# T962a-P1.net
KiCad netlist of a schematic drawn in Altium Designer
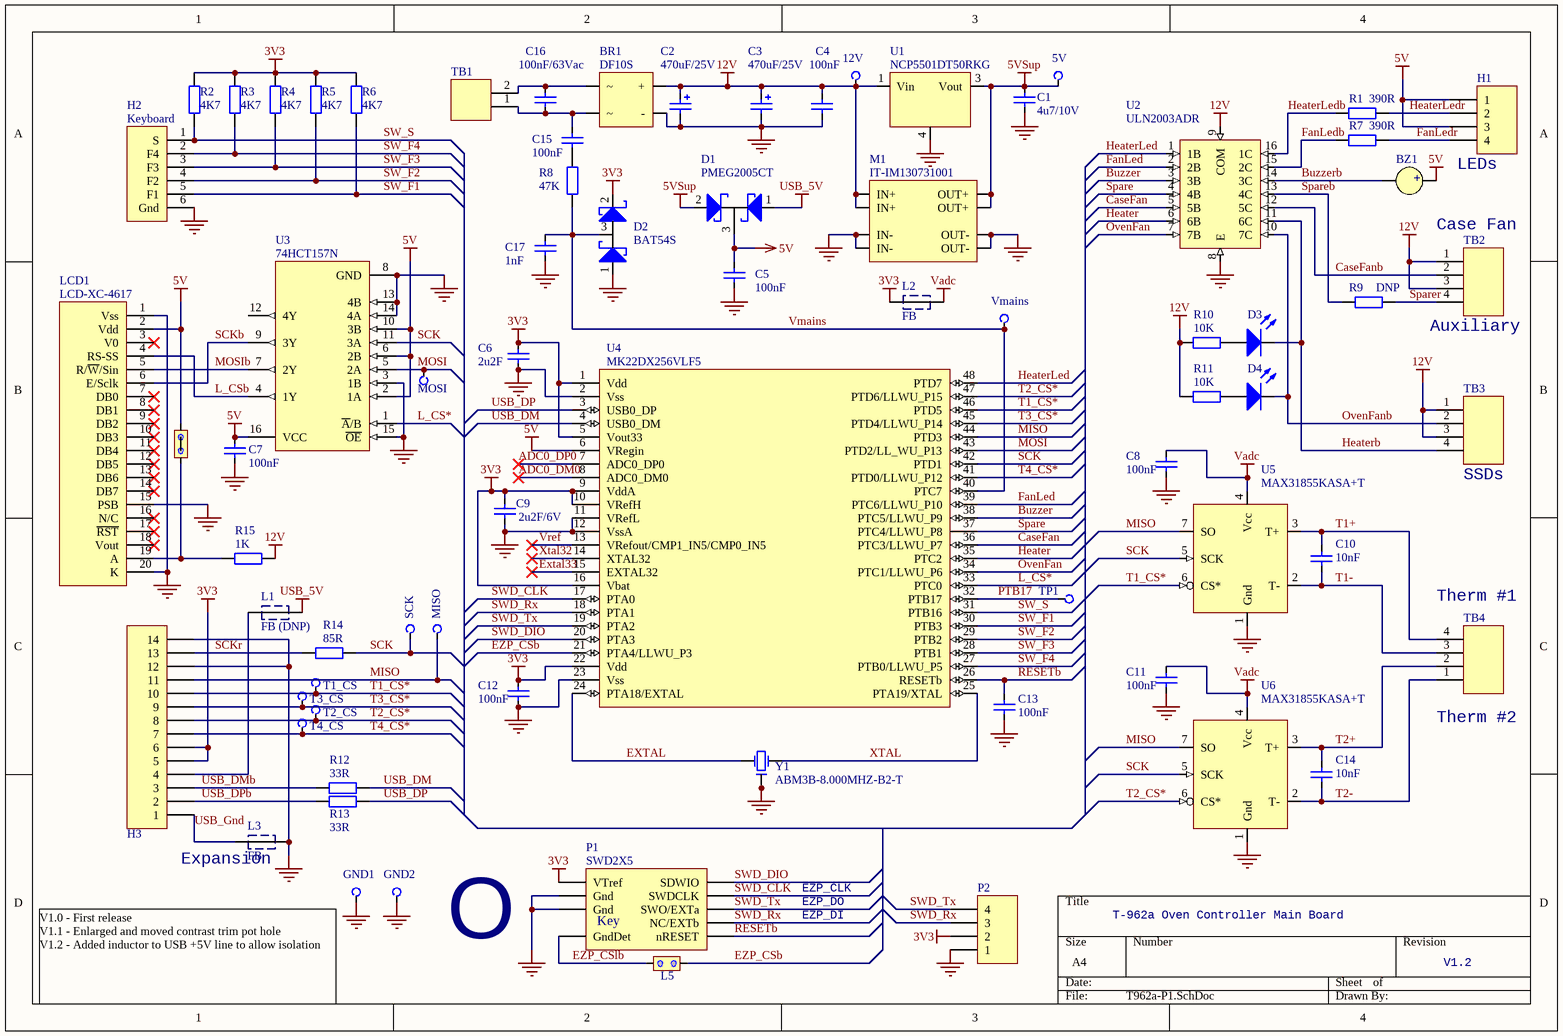
[diagram p0: T962a-P1.SchDoc]

(export (version "E")
  (design (tool "Eeschema 10.0.6"))
  (components
    (comp (ref "5V")
      (value "TP")
      (footprint "PCBPIN - 0.9mm")
      (description "Test Point")
      (libsource (lib "MyLibrary") (part "TP"))
    )
    (comp (ref "12V")
      (value "TP")
      (footprint "PCBPIN - 0.9mm")
      (description "Test Point")
      (libsource (lib "MyLibrary") (part "TP"))
    )
    (comp (ref "BR1")
      (value "DF10S")
      (footprint "Bridge-SMT")
      (description "bRIDGE rECTIFIER")
      (libsource (lib "MySchLib") (part "DF10S"))
    )
    (comp (ref "BZ1")
      (value "Buzzer_PCB")
      (footprint "BUZZER_Small")
      (description "Buzzer (Adafruit 1536)")
      (libsource (lib "MyLibrary") (part "Buzzer_PCB"))
    )
    (comp (ref "C1")
      (value "4u7/10V")
      (footprint "CCNP2012-0805")
      (description "Capacitor SMT 0805")
      (fields
        (field (name "MANUFACTURER") "Generic Components")
        (field (name "PUBLISHER") "Altium Hobart Technology Centre")
      )
      (libsource (lib "MyLibrary") (part "Cap_CCNP_0805"))
    )
    (comp (ref "C2")
      (value "470uF/25V")
      (footprint "RB5/10x13mm")
      (description "Polarized Capacitor")
      (fields
        (field (name "MANUFACTURER") "Generic Components")
        (field (name "PUBLISHER") "Altium Hobart Technology Centre")
      )
      (libsource (lib "MySchLib") (part "Cap-25ZLS470MEFC10X12"))
    )
    (comp (ref "C3")
      (value "470uF/25V")
      (footprint "RB5/10x13mm")
      (description "Polarized Capacitor")
      (fields
        (field (name "MANUFACTURER") "Generic Components")
        (field (name "PUBLISHER") "Altium Hobart Technology Centre")
      )
      (libsource (lib "MySchLib") (part "Cap-25ZLS470MEFC10X12"))
    )
    (comp (ref "C4")
      (value "100nF")
      (footprint "CCNP2012-0805")
      (description "Capacitor")
      (fields
        (field (name "MANUFACTURER") "Generic Components")
        (field (name "PUBLISHER") "Altium Hobart Technology Centre")
      )
      (libsource (lib "MyLibrary") (part "Cap"))
    )
    (comp (ref "C5")
      (value "100nF")
      (footprint "CCNP2012-0805")
      (description "Capacitor")
      (fields
        (field (name "MANUFACTURER") "Generic Components")
        (field (name "PUBLISHER") "Altium Hobart Technology Centre")
      )
      (libsource (lib "MyLibrary") (part "Cap"))
    )
    (comp (ref "C6")
      (value "2u2F")
      (footprint "CCNP2012-0805")
      (description "Capacitor")
      (fields
        (field (name "MANUFACTURER") "Generic Components")
        (field (name "PUBLISHER") "Altium Hobart Technology Centre")
      )
      (libsource (lib "MyLibrary") (part "Cap"))
    )
    (comp (ref "C7")
      (value "100nF")
      (footprint "CCNP2012-0805")
      (description "Capacitor")
      (fields
        (field (name "MANUFACTURER") "Generic Components")
        (field (name "PUBLISHER") "Altium Hobart Technology Centre")
      )
      (libsource (lib "MyLibrary") (part "Cap"))
    )
    (comp (ref "C8")
      (value "100nF")
      (footprint "CCNP2012-0805")
      (description "Capacitor SMT 0805")
      (fields
        (field (name "MANUFACTURER") "Generic Components")
        (field (name "PUBLISHER") "Altium Hobart Technology Centre")
      )
      (libsource (lib "MyLibrary") (part "Cap_CCNP_0805"))
    )
    (comp (ref "C9")
      (value "2u2F/6V")
      (footprint "CCNP2012-0805")
      (description "Capacitor")
      (fields
        (field (name "MANUFACTURER") "Generic Components")
        (field (name "PUBLISHER") "Altium Hobart Technology Centre")
      )
      (libsource (lib "MyLibrary") (part "Cap"))
    )
    (comp (ref "C10")
      (value "10nF")
      (footprint "CCNP2012-0805")
      (description "Capacitor SMT 0805")
      (fields
        (field (name "MANUFACTURER") "Generic Components")
        (field (name "PUBLISHER") "Altium Hobart Technology Centre")
      )
      (libsource (lib "MyLibrary") (part "Cap_CCNP_0805"))
    )
    (comp (ref "C11")
      (value "100nF")
      (footprint "CCNP2012-0805")
      (description "Capacitor SMT 0805")
      (fields
        (field (name "MANUFACTURER") "Generic Components")
        (field (name "PUBLISHER") "Altium Hobart Technology Centre")
      )
      (libsource (lib "MyLibrary") (part "Cap_CCNP_0805"))
    )
    (comp (ref "C12")
      (value "100nF")
      (footprint "CCNP2012-0805")
      (description "Capacitor")
      (fields
        (field (name "MANUFACTURER") "Generic Components")
        (field (name "PUBLISHER") "Altium Hobart Technology Centre")
      )
      (libsource (lib "MyLibrary") (part "Cap"))
    )
    (comp (ref "C13")
      (value "100nF")
      (footprint "CCNP2012-0805")
      (description "Capacitor SMT 0805")
      (fields
        (field (name "MANUFACTURER") "Generic Components")
        (field (name "PUBLISHER") "Altium Hobart Technology Centre")
      )
      (libsource (lib "MyLibrary") (part "Cap_CCNP_0805"))
    )
    (comp (ref "C14")
      (value "10nF")
      (footprint "CCNP2012-0805")
      (description "Capacitor SMT 0805")
      (fields
        (field (name "MANUFACTURER") "Generic Components")
        (field (name "PUBLISHER") "Altium Hobart Technology Centre")
      )
      (libsource (lib "MyLibrary") (part "Cap_CCNP_0805"))
    )
    (comp (ref "C15")
      (value "100nF")
      (footprint "CCNP2012-0805")
      (description "Capacitor")
      (fields
        (field (name "MANUFACTURER") "Generic Components")
        (field (name "PUBLISHER") "Altium Hobart Technology Centre")
      )
      (libsource (lib "MyLibrary") (part "Cap"))
    )
    (comp (ref "C16")
      (value "100nF/63Vac")
      (footprint "CAP - small MKT")
      (description "Capacitor")
      (fields
        (field (name "MANUFACTURER") "Generic Components")
        (field (name "PUBLISHER") "Altium Hobart Technology Centre")
      )
      (libsource (lib "MyLibrary") (part "Cap"))
    )
    (comp (ref "C17")
      (value "1nF")
      (footprint "CCNP2012-0805")
      (description "Capacitor")
      (fields
        (field (name "MANUFACTURER") "Generic Components")
        (field (name "PUBLISHER") "Altium Hobart Technology Centre")
      )
      (libsource (lib "MyLibrary") (part "Cap"))
    )
    (comp (ref "D1")
      (value "PMEG2005CT")
      (footprint "SOT23")
      (description "Dual Schottky Diode (SMT)")
      (libsource (lib "MyLibrary") (part "PMEG2005CT"))
    )
    (comp (ref "D2")
      (value "BAT54S")
      (footprint "SOT23")
      (description "Dual Diode (SMT)")
      (libsource (lib "MyLibrary") (part "BAT54S"))
    )
    (comp (ref "D3")
      (value "LED Red")
      (footprint "LED-SMT-2")
      (description "LED (Red SMT)")
      (fields (field (name "MANUFACTURER") "Generic Components") (field (name "PUBLISHER") "Altium Limited"))
      (libsource (lib "MyLibrary") (part "LED SMT,Red"))
    )
    (comp (ref "D4")
      (value "LED Red")
      (footprint "LED-SMT-2")
      (description "LED (Red SMT)")
      (fields (field (name "MANUFACTURER") "Generic Components") (field (name "PUBLISHER") "Altium Limited"))
      (libsource (lib "MyLibrary") (part "LED SMT,Red"))
    )
    (comp (ref "GND1")
      (value "TP")
      (footprint "PCBPIN - 0.9mm")
      (description "Test Point")
      (libsource (lib "MyLibrary") (part "TP"))
    )
    (comp (ref "GND2")
      (value "TP")
      (footprint "PCBPIN - 0.9mm")
      (description "Test Point")
      (libsource (lib "MyLibrary") (part "TP"))
    )
    (comp (ref "H1")
      (value "Header 1x4")
      (footprint "HDR1X4S")
      (description "Header, 5-Pin, Right Angle")
      (fields (field (name "PUBLISHER") "Altium Limited"))
      (libsource (lib "") (part "Header 1x4_1"))
    )
    (comp (ref "H2")
      (value "Keyboard")
      (footprint "HDR1X6H")
      (description "Header, 6-Pin")
      (fields (field (name "PUBLISHER") "Altium Limited"))
      (libsource (lib "Miscellaneous Connectors") (part "Header 6"))
    )
    (comp (ref "H3")
      (value "2x5 Header")
      (footprint "HDR2X7H")
      (description "Header 2x7")
      (libsource (lib "MyLibrary") (part "Header 2x7H"))
    )
    (comp (ref "L1")
      (value "FB (DNP)")
      (footprint "CR2012-0805")
      (description "Ferrite Bead (0805) 0.045OHM, 2A")
      (libsource (lib "MyLibrary") (part "Ferrite Bead 0805"))
    )
    (comp (ref "L2")
      (value "FB")
      (footprint "CR2012-0805")
      (description "Ferrite Bead (0805) 0.045OHM, 2A")
      (libsource (lib "MyLibrary") (part "Ferrite Bead 0805"))
    )
    (comp (ref "L3")
      (value "FB")
      (footprint "CR2012-0805")
      (description "Ferrite Bead (0805) 0.045OHM, 2A")
      (libsource (lib "MyLibrary") (part "Ferrite Bead 0805"))
    )
    (comp (ref "L5")
      (value "LinkOpen")
      (footprint "SolderBridge(Open)")
      (libsource (lib "MyLibrary") (part "LinkOpen"))
    )
    (comp (ref "L6")
      (value "LinkClosed")
      (footprint "SolderBridge(Closed)")
      (libsource (lib "MyLibrary") (part "LinkClosed"))
    )
    (comp (ref "LCD1")
      (value "LCD-XC-4617")
      (footprint "LCD_XC-4617")
      (description "LCD 128 x 64 pixel, ST7920 controller & contrast pot (Jaycar XC-4617)")
      (libsource (lib "MyLibrary") (part "LCD-XC-4617"))
    )
    (comp (ref "Logo1")
      (value "OSHW Logo")
      (footprint "OSHW")
      (libsource (lib "MyLibrary") (part "OSHW Logo"))
    )
    (comp (ref "M1")
      (value "IT-IM130731001")
      (footprint "IT-IM130731001")
      (description "Itead Buck converter")
      (libsource (lib "MyLibrary") (part "IT-IM130731001"))
    )
    (comp (ref "MISO")
      (value "TP")
      (footprint "PCBPIN - 0.9mm")
      (description "Test Point")
      (libsource (lib "MyLibrary") (part "TP"))
    )
    (comp (ref "MOSI")
      (value "TP")
      (footprint "PCBPIN - 0.9mm")
      (description "Test Point")
      (libsource (lib "MyLibrary") (part "TP"))
    )
    (comp (ref "P1")
      (value "SWD2X5")
      (footprint "SWD-2x5")
      (description "SWD Connector 2x5-Pin")
      (fields (field (name "PUBLISHER") "Altium Limited"))
      (libsource (lib "MySchLib") (part "SWD2X5"))
    )
    (comp (ref "P2")
      (value "Header 1x4")
      (footprint "HDR1X4S")
      (description "Header, 5-Pin, Right Angle")
      (fields (field (name "PUBLISHER") "Altium Limited"))
      (libsource (lib "MyLibrary") (part "Header 1x4"))
    )
    (comp (ref "R1")
      (value "390R")
      (footprint "CR2012-0805")
      (description "Resistor")
      (fields
        (field (name "MANUFACTURER") "Generic Components")
        (field (name "PUBLISHER") "Altium Hobart Technology Centre")
      )
      (libsource (lib "") (part "Res_CR0805_1"))
    )
    (comp (ref "R2")
      (value "4K7")
      (footprint "CR2012-0805")
      (description "Resistor")
      (fields
        (field (name "MANUFACTURER") "Generic Components")
        (field (name "PUBLISHER") "Altium Hobart Technology Centre")
      )
      (libsource (lib "MyLibrary") (part "Res_CR0805"))
    )
    (comp (ref "R3")
      (value "4K7")
      (footprint "CR2012-0805")
      (description "Resistor")
      (fields
        (field (name "MANUFACTURER") "Generic Components")
        (field (name "PUBLISHER") "Altium Hobart Technology Centre")
      )
      (libsource (lib "MyLibrary") (part "Res_CR0805"))
    )
    (comp (ref "R4")
      (value "4K7")
      (footprint "CR2012-0805")
      (description "Resistor")
      (fields
        (field (name "MANUFACTURER") "Generic Components")
        (field (name "PUBLISHER") "Altium Hobart Technology Centre")
      )
      (libsource (lib "MyLibrary") (part "Res_CR0805"))
    )
    (comp (ref "R5")
      (value "4K7")
      (footprint "CR2012-0805")
      (description "Resistor")
      (fields
        (field (name "MANUFACTURER") "Generic Components")
        (field (name "PUBLISHER") "Altium Hobart Technology Centre")
      )
      (libsource (lib "MyLibrary") (part "Res_CR0805"))
    )
    (comp (ref "R6")
      (value "4K7")
      (footprint "CR2012-0805")
      (description "Resistor")
      (fields
        (field (name "MANUFACTURER") "Generic Components")
        (field (name "PUBLISHER") "Altium Hobart Technology Centre")
      )
      (libsource (lib "MyLibrary") (part "Res_CR0805"))
    )
    (comp (ref "R7")
      (value "390R")
      (footprint "CR2012-0805")
      (description "Resistor")
      (fields
        (field (name "MANUFACTURER") "Generic Components")
        (field (name "PUBLISHER") "Altium Hobart Technology Centre")
      )
      (libsource (lib "") (part "Res_CR0805_1"))
    )
    (comp (ref "R8")
      (value "47K")
      (footprint "CR2012-0805")
      (description "Resistor")
      (fields
        (field (name "MANUFACTURER") "Generic Components")
        (field (name "PUBLISHER") "Altium Hobart Technology Centre")
      )
      (libsource (lib "MyLibrary") (part "Res_CR0805"))
    )
    (comp (ref "R9")
      (value "DNP")
      (footprint "CR2012-0805")
      (description "Resistor")
      (fields
        (field (name "MANUFACTURER") "Generic Components")
        (field (name "PUBLISHER") "Altium Hobart Technology Centre")
      )
      (libsource (lib "") (part "Res_CR0805_1"))
    )
    (comp (ref "R10")
      (value "10K")
      (footprint "CR2012-0805")
      (description "Resistor")
      (fields
        (field (name "MANUFACTURER") "Generic Components")
        (field (name "PUBLISHER") "Altium Hobart Technology Centre")
      )
      (libsource (lib "") (part "Res_CR0805_1"))
    )
    (comp (ref "R11")
      (value "10K")
      (footprint "CR2012-0805")
      (description "Resistor")
      (fields
        (field (name "MANUFACTURER") "Generic Components")
        (field (name "PUBLISHER") "Altium Hobart Technology Centre")
      )
      (libsource (lib "") (part "Res_CR0805_1"))
    )
    (comp (ref "R12")
      (value "33R")
      (footprint "CR2012-0805")
      (description "Resistor")
      (fields
        (field (name "MANUFACTURER") "Generic Components")
        (field (name "PUBLISHER") "Altium Hobart Technology Centre")
      )
      (libsource (lib "MyLibrary") (part "Res_CR0805"))
    )
    (comp (ref "R13")
      (value "33R")
      (footprint "CR2012-0805")
      (description "Resistor")
      (fields
        (field (name "MANUFACTURER") "Generic Components")
        (field (name "PUBLISHER") "Altium Hobart Technology Centre")
      )
      (libsource (lib "MyLibrary") (part "Res_CR0805"))
    )
    (comp (ref "R14")
      (value "85R")
      (footprint "CR2012-0805")
      (description "Resistor")
      (fields
        (field (name "MANUFACTURER") "Generic Components")
        (field (name "PUBLISHER") "Altium Hobart Technology Centre")
      )
      (libsource (lib "MyLibrary") (part "Res_CR0805"))
    )
    (comp (ref "R15")
      (value "1K")
      (footprint "CR2012-0805")
      (description "Resistor")
      (fields
        (field (name "MANUFACTURER") "Generic Components")
        (field (name "PUBLISHER") "Altium Hobart Technology Centre")
      )
      (libsource (lib "MyLibrary") (part "Res_CR0805"))
    )
    (comp (ref "SCK")
      (value "TP")
      (footprint "PCBPIN - 0.9mm")
      (description "Test Point")
      (libsource (lib "MyLibrary") (part "TP"))
    )
    (comp (ref "T1_CS")
      (value "TP")
      (footprint "PCBPIN - 0.9mm")
      (description "Test Point")
      (libsource (lib "MyLibrary") (part "TP"))
    )
    (comp (ref "T2_CS")
      (value "TP")
      (footprint "PCBPIN - 0.9mm")
      (description "Test Point")
      (libsource (lib "MyLibrary") (part "TP"))
    )
    (comp (ref "T3_CS")
      (value "TP")
      (footprint "PCBPIN - 0.9mm")
      (description "Test Point")
      (libsource (lib "MyLibrary") (part "TP"))
    )
    (comp (ref "T4_CS")
      (value "TP")
      (footprint "PCBPIN - 0.9mm")
      (description "Test Point")
      (libsource (lib "MyLibrary") (part "TP"))
    )
    (comp (ref "TB1")
      (value "Terminal2")
      (footprint "MOLEX-39544-3002")
      (description "MULTICOMP  MC24366 Wire-To-Board Terminal Block")
      (libsource (lib "MyLibrary") (part "Terminal2"))
    )
    (comp (ref "TB2")
      (value "Terminal4")
      (footprint "MOLEX-39544-3004")
      (description "MULTICOMP MC24368 Wire-To-Board Terminal Block")
      (libsource (lib "MyLibrary") (part "Terminal4"))
    )
    (comp (ref "TB3")
      (value "Terminal4")
      (footprint "MOLEX-39544-3004")
      (description "MULTICOMP MC24368 Wire-To-Board Terminal Block")
      (libsource (lib "MyLibrary") (part "Terminal4"))
    )
    (comp (ref "TB4")
      (value "Terminal4")
      (footprint "MOLEX-39544-3004")
      (description "MULTICOMP MC24368 Wire-To-Board Terminal Block")
      (libsource (lib "") (part "Terminal4_1"))
    )
    (comp (ref "TP1")
      (value "TP")
      (footprint "PCBPIN - 0.9mm")
      (description "Test Point")
      (libsource (lib "MyLibrary") (part "TP"))
    )
    (comp (ref "U1")
      (value "NCP5501DT50RKG")
      (footprint "TO-252")
      (description "Fixed LDO Voltage Regulator, 2.5V-16V in, 230mV Dropout, 5V/500mA out, TO-252-3")
      (libsource (lib "MyLibrary") (part "NCP5501DT50RKG"))
    )
    (comp (ref "U2")
      (value "ULN2003ADR")
      (footprint "SO-16_N")
      (libsource (lib "MyLibrary") (part "ULN2003ADR"))
    )
    (comp (ref "U3")
      (value "74HCT157N")
      (footprint "SO-16_N")
      (description "Quad 2-1 Multiplexor")
      (libsource (lib "MyLibrary") (part "74HCT157N"))
    )
    (comp (ref "U4")
      (value "MK22DX256VLF5")
      (footprint "TSQFP50P900X900-48M")
      (description "Arm Cortex M4")
      (libsource (lib "MyLibrary") (part "MK22DX256VLF5"))
    )
    (comp (ref "U5")
      (value "MAX31855KASA+T")
      (footprint "SO-8_L")
      (libsource (lib "MySchLib") (part "MAX31855KASA+T"))
    )
    (comp (ref "U6")
      (value "MAX31855KASA+T")
      (footprint "SO-8_L")
      (libsource (lib "MySchLib") (part "MAX31855KASA+T"))
    )
    (comp (ref "Vmains")
      (value "TP")
      (footprint "PCBPIN - 0.9mm")
      (description "Test Point")
      (libsource (lib "MyLibrary") (part "TP"))
    )
    (comp (ref "Y1")
      (value "ABM3B-8.000MHZ-B2-T")
      (footprint "Crystal_SMT - ABM3B")
      (description "Crystal 8MHz (MINIATURE SMT ABM3B)")
      (fields
        (field (name "MANUFACTURER") "Generic Components")
        (field (name "PUBLISHER") "Altium Hobart Technology Centre")
      )
      (libsource (lib "MyLibrary") (part "ABM3B-8.000MHZ-B2-T"))
    )
  )
  (nets
    (net (code "1") (name "/ADC0_DM0") (class "Default")
      (node (ref "U4") (pin "8") (pinfunction "ADC0_DM0_8") (pintype "passive+no_connect"))
    )
    (net (code "2") (name "/ADC0_DP0") (class "Default")
      (node (ref "U4") (pin "7") (pinfunction "ADC0_DP0_7") (pintype "passive+no_connect"))
    )
    (net (code "3") (name "/Buzzer") (class "Default")
      (node (ref "U2") (pin "3") (pinfunction "3B_3") (pintype "input"))
      (node (ref "U4") (pin "38") (pinfunction "PTC5/LLWU_P9_38") (pintype "bidirectional"))
    )
    (net (code "4") (name "/Buzzerb") (class "Default")
      (node (ref "BZ1") (pin "1") (pinfunction "1_1") (pintype "passive"))
      (node (ref "U2") (pin "14") (pinfunction "3C_14") (pintype "input"))
    )
    (net (code "5") (name "/CaseFan") (class "Default")
      (node (ref "U2") (pin "5") (pinfunction "5B_5") (pintype "input"))
      (node (ref "U4") (pin "36") (pinfunction "PTC3/LLWU_P7_36") (pintype "bidirectional"))
    )
    (net (code "6") (name "/CaseFanb") (class "Default")
      (node (ref "TB2") (pin "2") (pinfunction "2_2") (pintype "passive"))
      (node (ref "U2") (pin "12") (pinfunction "5C_12") (pintype "input"))
    )
    (net (code "7") (name "/EXTAL") (class "Default")
      (node (ref "U4") (pin "24") (pinfunction "PTA18/EXTAL_24") (pintype "bidirectional"))
      (node (ref "Y1") (pin "1") (pinfunction "OSC1_1") (pintype "passive"))
    )
    (net (code "8") (name "/EZP_CSb") (class "Default")
      (node (ref "L5") (pin "2") (pintype "passive"))
      (node (ref "U4") (pin "21") (pinfunction "PTA4/LLWU_P3_21") (pintype "bidirectional"))
    )
    (net (code "9") (name "/EZP_CSlb") (class "Default")
      (node (ref "L5") (pin "1") (pintype "passive"))
      (node (ref "P1") (pin "9") (pinfunction "GndDet_9") (pintype "passive"))
    )
    (net (code "10") (name "/Extal33") (class "Default")
      (node (ref "U4") (pin "15") (pinfunction "EXTAL32_15") (pintype "passive+no_connect"))
    )
    (net (code "11") (name "/FanLed") (class "Default")
      (node (ref "U2") (pin "2") (pinfunction "2B_2") (pintype "input"))
      (node (ref "U4") (pin "39") (pinfunction "PTC6/LLWU_P10_39") (pintype "bidirectional"))
    )
    (net (code "12") (name "/FanLedb") (class "Default")
      (node (ref "R7") (pin "1") (pinfunction "1_1") (pintype "passive"))
      (node (ref "U2") (pin "15") (pinfunction "2C_15") (pintype "input"))
    )
    (net (code "13") (name "/FanLedr") (class "Default")
      (node (ref "H1") (pin "4") (pinfunction "4_4") (pintype "passive"))
      (node (ref "R7") (pin "2") (pinfunction "2_2") (pintype "passive"))
    )
    (net (code "14") (name "/Heater") (class "Default")
      (node (ref "U2") (pin "6") (pinfunction "6B_6") (pintype "input"))
      (node (ref "U4") (pin "35") (pinfunction "PTC2_35") (pintype "bidirectional"))
    )
    (net (code "15") (name "/HeaterLed") (class "Default")
      (node (ref "U2") (pin "1") (pinfunction "1B_1") (pintype "input"))
      (node (ref "U4") (pin "48") (pinfunction "PTD7_48") (pintype "bidirectional"))
    )
    (net (code "16") (name "/HeaterLedb") (class "Default")
      (node (ref "R1") (pin "1") (pinfunction "1_1") (pintype "passive"))
      (node (ref "U2") (pin "16") (pinfunction "1C_16") (pintype "input"))
    )
    (net (code "17") (name "/HeaterLedr") (class "Default")
      (node (ref "H1") (pin "2") (pinfunction "2_2") (pintype "passive"))
      (node (ref "R1") (pin "2") (pinfunction "2_2") (pintype "passive"))
    )
    (net (code "18") (name "/Heaterb") (class "Default")
      (node (ref "D3") (pin "K") (pinfunction "K_K") (pintype "passive"))
      (node (ref "TB3") (pin "4") (pinfunction "4_4") (pintype "passive"))
      (node (ref "U2") (pin "11") (pinfunction "6C_11") (pintype "input"))
    )
    (net (code "19") (name "/L_CS*") (class "Default")
      (node (ref "U3") (pin "1") (pinfunction "~{A}/B_1") (pintype "input"))
      (node (ref "U4") (pin "33") (pinfunction "PTC0_33") (pintype "bidirectional"))
    )
    (net (code "20") (name "/L_CSb") (class "Default")
      (node (ref "LCD1") (pin "4") (pinfunction "RS-SS_4") (pintype "passive"))
      (node (ref "U3") (pin "4") (pinfunction "1Y_4") (pintype "output"))
    )
    (net (code "21") (name "/MISO") (class "Default")
      (node (ref "H3") (pin "11") (pinfunction "11_11") (pintype "passive"))
      (node (ref "MISO") (pin "1") (pinfunction "TP_1") (pintype "passive"))
      (node (ref "U4") (pin "44") (pinfunction "PTD3_44") (pintype "bidirectional"))
      (node (ref "U5") (pin "7") (pinfunction "SO_7") (pintype "tri_state"))
      (node (ref "U6") (pin "7") (pinfunction "SO_7") (pintype "tri_state"))
    )
    (net (code "22") (name "/MOSI") (class "Default")
      (node (ref "MOSI") (pin "1") (pinfunction "TP_1") (pintype "passive"))
      (node (ref "U3") (pin "5") (pinfunction "2A_5") (pintype "input"))
      (node (ref "U4") (pin "43") (pinfunction "PTD2/LL_WU_P13_43") (pintype "bidirectional"))
    )
    (net (code "23") (name "/MOSIb") (class "Default")
      (node (ref "LCD1") (pin "5") (pinfunction "R/~{W}/Sin_5") (pintype "passive"))
      (node (ref "U3") (pin "7") (pinfunction "2Y_7") (pintype "output"))
    )
    (net (code "24") (name "/OvenFan") (class "Default")
      (node (ref "U2") (pin "7") (pinfunction "7B_7") (pintype "input"))
      (node (ref "U4") (pin "34") (pinfunction "PTC1/LLWU_P6_34") (pintype "bidirectional"))
    )
    (net (code "25") (name "/OvenFanb") (class "Default")
      (node (ref "D4") (pin "K") (pinfunction "K_K") (pintype "passive"))
      (node (ref "TB3") (pin "2") (pinfunction "2_2") (pintype "passive"))
      (node (ref "U2") (pin "10") (pinfunction "7C_10") (pintype "input"))
    )
    (net (code "26") (name "/PTB17") (class "Default")
      (node (ref "TP1") (pin "1") (pinfunction "TP_1") (pintype "passive"))
      (node (ref "U4") (pin "32") (pinfunction "PTB17_32") (pintype "bidirectional"))
    )
    (net (code "27") (name "/RESETb") (class "Default")
      (node (ref "C13") (pin "2") (pinfunction "2_2") (pintype "passive"))
      (node (ref "P1") (pin "10") (pinfunction "nRESET_10") (pintype "passive"))
      (node (ref "U4") (pin "26") (pinfunction "RESETb_26") (pintype "bidirectional"))
    )
    (net (code "28") (name "/SCK") (class "Default")
      (node (ref "R14") (pin "2") (pinfunction "2_2") (pintype "passive"))
      (node (ref "SCK") (pin "1") (pinfunction "TP_1") (pintype "passive"))
      (node (ref "U3") (pin "11") (pinfunction "3A_11") (pintype "input"))
      (node (ref "U4") (pin "42") (pinfunction "PTD1_42") (pintype "bidirectional"))
      (node (ref "U5") (pin "5") (pinfunction "SCK_5") (pintype "input"))
      (node (ref "U6") (pin "5") (pinfunction "SCK_5") (pintype "input"))
    )
    (net (code "29") (name "/SCKb") (class "Default")
      (node (ref "LCD1") (pin "6") (pinfunction "E/Sclk_6") (pintype "passive"))
      (node (ref "U3") (pin "9") (pinfunction "3Y_9") (pintype "output"))
    )
    (net (code "30") (name "/SCKr") (class "Default")
      (node (ref "H3") (pin "13") (pinfunction "13_13") (pintype "passive"))
      (node (ref "R14") (pin "1") (pinfunction "1_1") (pintype "passive"))
    )
    (net (code "31") (name "/SWD_CLK") (class "Default")
      (node (ref "P1") (pin "4") (pinfunction "SWDCLK_4") (pintype "passive"))
      (node (ref "U4") (pin "17") (pinfunction "PTA0_17") (pintype "bidirectional"))
    )
    (net (code "32") (name "/SWD_DIO") (class "Default")
      (node (ref "P1") (pin "2") (pinfunction "SDWIO_2") (pintype "passive"))
      (node (ref "U4") (pin "20") (pinfunction "PTA3_20") (pintype "bidirectional"))
    )
    (net (code "33") (name "/SWD_Rx") (class "Default")
      (node (ref "P1") (pin "8") (pinfunction "NC/EXTb_8") (pintype "passive"))
      (node (ref "P2") (pin "3") (pinfunction "3_3") (pintype "passive"))
      (node (ref "U4") (pin "18") (pinfunction "PTA1_18") (pintype "bidirectional"))
    )
    (net (code "34") (name "/SWD_Tx") (class "Default")
      (node (ref "P1") (pin "6") (pinfunction "SWO/EXTa_6") (pintype "passive"))
      (node (ref "P2") (pin "4") (pinfunction "4_4") (pintype "passive"))
      (node (ref "U4") (pin "19") (pinfunction "PTA2_19") (pintype "bidirectional"))
    )
    (net (code "35") (name "/SW_F1") (class "Default")
      (node (ref "H2") (pin "5") (pinfunction "F1_5") (pintype "passive"))
      (node (ref "R6") (pin "1") (pinfunction "1_1") (pintype "passive"))
      (node (ref "U4") (pin "30") (pinfunction "PTB3_30") (pintype "bidirectional"))
    )
    (net (code "36") (name "/SW_F2") (class "Default")
      (node (ref "H2") (pin "4") (pinfunction "F2_4") (pintype "passive"))
      (node (ref "R5") (pin "1") (pinfunction "1_1") (pintype "passive"))
      (node (ref "U4") (pin "29") (pinfunction "PTB2_29") (pintype "bidirectional"))
    )
    (net (code "37") (name "/SW_F3") (class "Default")
      (node (ref "H2") (pin "3") (pinfunction "F3_3") (pintype "passive"))
      (node (ref "R4") (pin "1") (pinfunction "1_1") (pintype "passive"))
      (node (ref "U4") (pin "28") (pinfunction "PTB1_28") (pintype "bidirectional"))
    )
    (net (code "38") (name "/SW_F4") (class "Default")
      (node (ref "H2") (pin "2") (pinfunction "F4_2") (pintype "passive"))
      (node (ref "R3") (pin "1") (pinfunction "1_1") (pintype "passive"))
      (node (ref "U4") (pin "27") (pinfunction "PTB0/LLWU_P5_27") (pintype "bidirectional"))
    )
    (net (code "39") (name "/SW_S") (class "Default")
      (node (ref "H2") (pin "1") (pinfunction "S_1") (pintype "passive"))
      (node (ref "R2") (pin "1") (pinfunction "1_1") (pintype "passive"))
      (node (ref "U4") (pin "31") (pinfunction "PTB16_31") (pintype "bidirectional"))
    )
    (net (code "40") (name "/Spare") (class "Default")
      (node (ref "U2") (pin "4") (pinfunction "4B_4") (pintype "input"))
      (node (ref "U4") (pin "37") (pinfunction "PTC4/LLWU_P8_37") (pintype "power_in"))
    )
    (net (code "41") (name "/Spareb") (class "Default")
      (node (ref "R9") (pin "1") (pinfunction "1_1") (pintype "passive"))
      (node (ref "U2") (pin "13") (pinfunction "4C_13") (pintype "input"))
    )
    (net (code "42") (name "/Sparer") (class "Default")
      (node (ref "R9") (pin "2") (pinfunction "2_2") (pintype "passive"))
      (node (ref "TB2") (pin "4") (pinfunction "4_4") (pintype "passive"))
    )
    (net (code "43") (name "/T1+") (class "Default")
      (node (ref "C10") (pin "2") (pinfunction "2_2") (pintype "passive"))
      (node (ref "TB4") (pin "4") (pinfunction "4_4") (pintype "passive"))
      (node (ref "U5") (pin "3") (pinfunction "T+_3") (pintype "passive"))
    )
    (net (code "44") (name "/T1-") (class "Default")
      (node (ref "C10") (pin "1") (pinfunction "1_1") (pintype "passive"))
      (node (ref "TB4") (pin "3") (pinfunction "3_3") (pintype "passive"))
      (node (ref "U5") (pin "2") (pinfunction "T-_2") (pintype "passive"))
    )
    (net (code "45") (name "/T1_CS*") (class "Default")
      (node (ref "H3") (pin "10") (pinfunction "10_10") (pintype "passive"))
      (node (ref "T1_CS") (pin "1") (pinfunction "TP_1") (pintype "passive"))
      (node (ref "U4") (pin "46") (pinfunction "PTD5_46") (pintype "bidirectional"))
      (node (ref "U5") (pin "6") (pinfunction "CS*_6") (pintype "input"))
    )
    (net (code "46") (name "/T2+") (class "Default")
      (node (ref "C14") (pin "2") (pinfunction "2_2") (pintype "passive"))
      (node (ref "TB4") (pin "2") (pinfunction "2_2") (pintype "passive"))
      (node (ref "U6") (pin "3") (pinfunction "T+_3") (pintype "passive"))
    )
    (net (code "47") (name "/T2-") (class "Default")
      (node (ref "C14") (pin "1") (pinfunction "1_1") (pintype "passive"))
      (node (ref "TB4") (pin "1") (pinfunction "1_1") (pintype "passive"))
      (node (ref "U6") (pin "2") (pinfunction "T-_2") (pintype "passive"))
    )
    (net (code "48") (name "/T2_CS*") (class "Default")
      (node (ref "H3") (pin "8") (pinfunction "8_8") (pintype "passive"))
      (node (ref "T2_CS") (pin "1") (pinfunction "TP_1") (pintype "passive"))
      (node (ref "U4") (pin "47") (pinfunction "PTD6/LLWU_P15_47") (pintype "bidirectional"))
      (node (ref "U6") (pin "6") (pinfunction "CS*_6") (pintype "input"))
    )
    (net (code "49") (name "/T3_CS*") (class "Default")
      (node (ref "H3") (pin "9") (pinfunction "9_9") (pintype "passive"))
      (node (ref "T3_CS") (pin "1") (pinfunction "TP_1") (pintype "passive"))
      (node (ref "U4") (pin "45") (pinfunction "PTD4/LLWU_P14_45") (pintype "bidirectional"))
    )
    (net (code "50") (name "/T4_CS*") (class "Default")
      (node (ref "H3") (pin "7") (pinfunction "7_7") (pintype "passive"))
      (node (ref "T4_CS") (pin "1") (pinfunction "TP_1") (pintype "passive"))
      (node (ref "U4") (pin "41") (pinfunction "PTD0/LLWU_P12_41") (pintype "bidirectional"))
    )
    (net (code "51") (name "/USB_DM") (class "Default")
      (node (ref "R12") (pin "2") (pinfunction "2_2") (pintype "passive"))
      (node (ref "U4") (pin "4") (pinfunction "USB0_DM_4") (pintype "bidirectional"))
    )
    (net (code "52") (name "/USB_DMb") (class "Default")
      (node (ref "H3") (pin "3") (pinfunction "3_3") (pintype "passive"))
      (node (ref "R12") (pin "1") (pinfunction "1_1") (pintype "passive"))
    )
    (net (code "53") (name "/USB_DP") (class "Default")
      (node (ref "R13") (pin "2") (pinfunction "2_2") (pintype "passive"))
      (node (ref "U4") (pin "3") (pinfunction "USB0_DP_3") (pintype "bidirectional"))
    )
    (net (code "54") (name "/USB_DPb") (class "Default")
      (node (ref "H3") (pin "2") (pinfunction "2_2") (pintype "passive"))
      (node (ref "R13") (pin "1") (pinfunction "1_1") (pintype "passive"))
    )
    (net (code "55") (name "/USB_Gnd") (class "Default")
      (node (ref "H3") (pin "1") (pinfunction "1_1") (pintype "passive"))
      (node (ref "L3") (pin "2") (pinfunction "2_2") (pintype "passive"))
    )
    (net (code "56") (name "/Vmains") (class "Default")
      (node (ref "C17") (pin "2") (pinfunction "2_2") (pintype "passive"))
      (node (ref "D2") (pin "3") (pinfunction "K_3") (pintype "passive"))
      (node (ref "R8") (pin "1") (pinfunction "1_1") (pintype "passive"))
      (node (ref "U4") (pin "40") (pinfunction "PTC7_40") (pintype "bidirectional"))
      (node (ref "Vmains") (pin "1") (pinfunction "TP_1") (pintype "passive"))
    )
    (net (code "57") (name "/Vref") (class "Default")
      (node (ref "U4") (pin "13") (pinfunction "VRefout/CMP1_IN5/CMP0_IN5_13") (pintype "passive+no_connect"))
    )
    (net (code "58") (name "/XTAL") (class "Default")
      (node (ref "U4") (pin "25") (pinfunction "PTA19/XTAL_25") (pintype "bidirectional"))
      (node (ref "Y1") (pin "3") (pinfunction "OSC2_3") (pintype "passive"))
    )
    (net (code "59") (name "/Xtal32") (class "Default")
      (node (ref "U4") (pin "14") (pinfunction "XTAL32_14") (pintype "passive+no_connect"))
    )
    (net (code "60") (name "3V3") (class "Default")
      (node (ref "C12") (pin "2") (pinfunction "2_2") (pintype "passive"))
      (node (ref "C6") (pin "2") (pinfunction "2_2") (pintype "passive"))
      (node (ref "C9") (pin "2") (pinfunction "2_2") (pintype "passive"))
      (node (ref "D2") (pin "2") (pinfunction "A2_2") (pintype "passive"))
      (node (ref "H3") (pin "5") (pinfunction "5_5") (pintype "passive"))
      (node (ref "H3") (pin "6") (pinfunction "6_6") (pintype "passive"))
      (node (ref "L2") (pin "1") (pinfunction "1_1") (pintype "passive"))
      (node (ref "P1") (pin "1") (pinfunction "VTref_1") (pintype "passive"))
      (node (ref "P2") (pin "2") (pinfunction "2_2") (pintype "passive"))
      (node (ref "R2") (pin "2") (pinfunction "2_2") (pintype "passive"))
      (node (ref "R3") (pin "2") (pinfunction "2_2") (pintype "passive"))
      (node (ref "R4") (pin "2") (pinfunction "2_2") (pintype "passive"))
      (node (ref "R5") (pin "2") (pinfunction "2_2") (pintype "passive"))
      (node (ref "R6") (pin "2") (pinfunction "2_2") (pintype "passive"))
      (node (ref "U4") (pin "1") (pinfunction "Vdd_1") (pintype "power_in"))
      (node (ref "U4") (pin "10") (pinfunction "VRefH_10") (pintype "passive"))
      (node (ref "U4") (pin "16") (pinfunction "Vbat_16") (pintype "passive"))
      (node (ref "U4") (pin "22") (pinfunction "Vdd_22") (pintype "power_in"))
      (node (ref "U4") (pin "5") (pinfunction "Vout33_5") (pintype "power_in"))
      (node (ref "U4") (pin "9") (pinfunction "VddA_9") (pintype "power_in"))
    )
    (net (code "61") (name "5V") (class "Default")
      (node (ref "BZ1") (pin "2") (pinfunction "+_2") (pintype "passive"))
      (node (ref "C5") (pin "2") (pinfunction "2_2") (pintype "passive"))
      (node (ref "C7") (pin "2") (pinfunction "2_2") (pintype "passive"))
      (node (ref "D1") (pin "3") (pinfunction "K_3") (pintype "passive"))
      (node (ref "H1") (pin "1") (pinfunction "1_1") (pintype "passive"))
      (node (ref "H1") (pin "3") (pinfunction "3_3") (pintype "passive"))
      (node (ref "L6") (pin "2") (pintype "passive"))
      (node (ref "LCD1") (pin "2") (pinfunction "Vdd_2") (pintype "passive"))
      (node (ref "U3") (pin "10") (pinfunction "3B_10") (pintype "input"))
      (node (ref "U3") (pin "16") (pinfunction "VCC_16") (pintype "power_in"))
      (node (ref "U3") (pin "2") (pinfunction "1A_2") (pintype "input"))
      (node (ref "U3") (pin "6") (pinfunction "2B_6") (pintype "input"))
      (node (ref "U4") (pin "6") (pinfunction "VRegin_6") (pintype "passive"))
    )
    (net (code "62") (name "5VSup") (class "Default")
      (node (ref "5V") (pin "1") (pinfunction "TP_1") (pintype "passive"))
      (node (ref "C1") (pin "2") (pinfunction "2_2") (pintype "passive"))
      (node (ref "D1") (pin "2") (pinfunction "A2_2") (pintype "passive"))
      (node (ref "M1") (pin "OUT0+") (pinfunction "OUT+_OUT0+") (pintype "power_in"))
      (node (ref "M1") (pin "OUT1+") (pinfunction "OUT+_OUT1+") (pintype "power_in"))
      (node (ref "U1") (pin "3") (pinfunction "Vout_3") (pintype "passive"))
    )
    (net (code "63") (name "12V") (class "Default")
      (node (ref "12V") (pin "1") (pinfunction "TP_1") (pintype "passive"))
      (node (ref "BR1") (pin "1") (pinfunction "+_1") (pintype "power_in"))
      (node (ref "C2") (pin "1") (pinfunction "1_1") (pintype "passive"))
      (node (ref "C3") (pin "1") (pinfunction "1_1") (pintype "passive"))
      (node (ref "C4") (pin "2") (pinfunction "2_2") (pintype "passive"))
      (node (ref "M1") (pin "IN0+") (pinfunction "IN+_IN0+") (pintype "power_in"))
      (node (ref "M1") (pin "IN1+") (pinfunction "IN+_IN1+") (pintype "power_in"))
      (node (ref "R10") (pin "1") (pinfunction "1_1") (pintype "passive"))
      (node (ref "R11") (pin "1") (pinfunction "1_1") (pintype "passive"))
      (node (ref "R15") (pin "2") (pinfunction "2_2") (pintype "passive"))
      (node (ref "TB2") (pin "1") (pinfunction "1_1") (pintype "passive"))
      (node (ref "TB2") (pin "3") (pinfunction "3_3") (pintype "passive"))
      (node (ref "TB3") (pin "1") (pinfunction "1_1") (pintype "passive"))
      (node (ref "TB3") (pin "3") (pinfunction "3_3") (pintype "passive"))
      (node (ref "U1") (pin "1") (pinfunction "Vin_1") (pintype "passive"))
      (node (ref "U2") (pin "9") (pinfunction "COM_9") (pintype "input"))
    )
    (net (code "64") (name "GND") (class "Default")
      (node (ref "BR1") (pin "2") (pinfunction "-_2") (pintype "power_in"))
      (node (ref "C1") (pin "1") (pinfunction "1_1") (pintype "passive"))
      (node (ref "C11") (pin "1") (pinfunction "1_1") (pintype "passive"))
      (node (ref "C12") (pin "1") (pinfunction "1_1") (pintype "passive"))
      (node (ref "C13") (pin "1") (pinfunction "1_1") (pintype "passive"))
      (node (ref "C17") (pin "1") (pinfunction "1_1") (pintype "passive"))
      (node (ref "C2") (pin "2") (pinfunction "2_2") (pintype "passive"))
      (node (ref "C3") (pin "2") (pinfunction "2_2") (pintype "passive"))
      (node (ref "C4") (pin "1") (pinfunction "1_1") (pintype "passive"))
      (node (ref "C5") (pin "1") (pinfunction "1_1") (pintype "passive"))
      (node (ref "C6") (pin "1") (pinfunction "1_1") (pintype "passive"))
      (node (ref "C7") (pin "1") (pinfunction "1_1") (pintype "passive"))
      (node (ref "C8") (pin "1") (pinfunction "1_1") (pintype "passive"))
      (node (ref "C9") (pin "1") (pinfunction "1_1") (pintype "passive"))
      (node (ref "D2") (pin "1") (pinfunction "A1_1") (pintype "passive"))
      (node (ref "GND1") (pin "1") (pinfunction "TP_1") (pintype "passive"))
      (node (ref "GND2") (pin "1") (pinfunction "TP_1") (pintype "passive"))
      (node (ref "H2") (pin "6") (pinfunction "Gnd_6") (pintype "passive"))
      (node (ref "H3") (pin "12") (pinfunction "12_12") (pintype "passive"))
      (node (ref "H3") (pin "14") (pinfunction "14_14") (pintype "passive"))
      (node (ref "L3") (pin "1") (pinfunction "1_1") (pintype "passive"))
      (node (ref "LCD1") (pin "1") (pinfunction "Vss_1") (pintype "passive"))
      (node (ref "LCD1") (pin "15") (pinfunction "PSB_15") (pintype "passive"))
      (node (ref "LCD1") (pin "20") (pinfunction "K_20") (pintype "passive"))
      (node (ref "M1") (pin "IN0-") (pinfunction "IN-_IN0-") (pintype "power_in"))
      (node (ref "M1") (pin "IN1-") (pinfunction "IN-_IN1-") (pintype "power_in"))
      (node (ref "M1") (pin "OUT0-") (pinfunction "OUT-_OUT0-") (pintype "power_in"))
      (node (ref "M1") (pin "OUT1-") (pinfunction "OUT-_OUT1-") (pintype "power_in"))
      (node (ref "P1") (pin "3") (pinfunction "Gnd_3") (pintype "passive"))
      (node (ref "P1") (pin "5") (pinfunction "Gnd_5") (pintype "passive"))
      (node (ref "P2") (pin "1") (pinfunction "1_1") (pintype "passive"))
      (node (ref "U1") (pin "4") (pinfunction "Gnd_(Tab)_4") (pintype "power_in"))
      (node (ref "U2") (pin "8") (pinfunction "E_8") (pintype "input"))
      (node (ref "U3") (pin "13") (pinfunction "4B_13") (pintype "input"))
      (node (ref "U3") (pin "14") (pinfunction "4A_14") (pintype "input"))
      (node (ref "U3") (pin "15") (pinfunction "~{OE}_15") (pintype "input"))
      (node (ref "U3") (pin "3") (pinfunction "1B_3") (pintype "input"))
      (node (ref "U3") (pin "8") (pinfunction "GND_8") (pintype "power_in"))
      (node (ref "U4") (pin "11") (pinfunction "VRefL_11") (pintype "passive"))
      (node (ref "U4") (pin "12") (pinfunction "VssA_12") (pintype "power_in"))
      (node (ref "U4") (pin "2") (pinfunction "Vss_2") (pintype "power_in"))
      (node (ref "U4") (pin "23") (pinfunction "Vss_23") (pintype "power_in"))
      (node (ref "U5") (pin "1") (pinfunction "Gnd_1") (pintype "power_in"))
      (node (ref "U6") (pin "1") (pinfunction "Gnd_1") (pintype "power_in"))
      (node (ref "Y1") (pin "2") (pinfunction "Gnd_2") (pintype "passive"))
      (node (ref "Y1") (pin "4") (pinfunction "Gnd_4") (pintype "passive"))
    )
    (net (code "65") (name "Net-(BR1-~-Pad3)") (class "Default")
      (node (ref "BR1") (pin "3") (pinfunction "~_3") (pintype "power_in"))
      (node (ref "C15") (pin "2") (pinfunction "2_2") (pintype "passive"))
      (node (ref "C16") (pin "1") (pinfunction "1_1") (pintype "passive"))
      (node (ref "TB1") (pin "1") (pinfunction "1_1") (pintype "passive"))
    )
    (net (code "66") (name "Net-(BR1-~-Pad4)") (class "Default")
      (node (ref "BR1") (pin "4") (pinfunction "~_4") (pintype "power_in"))
      (node (ref "C16") (pin "2") (pinfunction "2_2") (pintype "passive"))
      (node (ref "TB1") (pin "2") (pinfunction "2_2") (pintype "passive"))
    )
    (net (code "67") (name "Net-(C15-Pad1)") (class "Default")
      (node (ref "C15") (pin "1") (pinfunction "1_1") (pintype "passive"))
      (node (ref "R8") (pin "2") (pinfunction "2_2") (pintype "passive"))
    )
    (net (code "68") (name "Net-(D3-PadA)") (class "Default")
      (node (ref "D3") (pin "A") (pinfunction "A_A") (pintype "passive"))
      (node (ref "R10") (pin "2") (pinfunction "2_2") (pintype "passive"))
    )
    (net (code "69") (name "Net-(D4-PadA)") (class "Default")
      (node (ref "D4") (pin "A") (pinfunction "A_A") (pintype "passive"))
      (node (ref "R11") (pin "2") (pinfunction "2_2") (pintype "passive"))
    )
    (net (code "70") (name "Net-(H3-Pad4)") (class "Default")
      (node (ref "H3") (pin "4") (pinfunction "4_4") (pintype "passive"))
      (node (ref "L1") (pin "2") (pinfunction "2_2") (pintype "passive"))
    )
    (net (code "71") (name "Net-(LCD1-A)") (class "Default")
      (node (ref "L6") (pin "1") (pintype "passive"))
      (node (ref "LCD1") (pin "19") (pinfunction "A_19") (pintype "passive"))
      (node (ref "R15") (pin "1") (pinfunction "1_1") (pintype "passive"))
    )
    (net (code "72") (name "USB_5V") (class "Default")
      (node (ref "D1") (pin "1") (pinfunction "A1_1") (pintype "passive"))
      (node (ref "L1") (pin "1") (pinfunction "1_1") (pintype "passive"))
    )
    (net (code "73") (name "Vadc") (class "Default")
      (node (ref "C11") (pin "2") (pinfunction "2_2") (pintype "passive"))
      (node (ref "C8") (pin "2") (pinfunction "2_2") (pintype "passive"))
      (node (ref "L2") (pin "2") (pinfunction "2_2") (pintype "passive"))
      (node (ref "U5") (pin "4") (pinfunction "Vcc_4") (pintype "power_in"))
      (node (ref "U6") (pin "4") (pinfunction "Vcc_4") (pintype "power_in"))
    )
    (net (code "74") (name "unconnected-(LCD1-DB0-Pad7)") (class "Default")
      (node (ref "LCD1") (pin "7") (pinfunction "DB0_7") (pintype "passive+no_connect"))
    )
    (net (code "75") (name "unconnected-(LCD1-DB1-Pad8)") (class "Default")
      (node (ref "LCD1") (pin "8") (pinfunction "DB1_8") (pintype "passive+no_connect"))
    )
    (net (code "76") (name "unconnected-(LCD1-DB2-Pad9)") (class "Default")
      (node (ref "LCD1") (pin "9") (pinfunction "DB2_9") (pintype "passive+no_connect"))
    )
    (net (code "77") (name "unconnected-(LCD1-DB3-Pad10)") (class "Default")
      (node (ref "LCD1") (pin "10") (pinfunction "DB3_10") (pintype "passive+no_connect"))
    )
    (net (code "78") (name "unconnected-(LCD1-DB4-Pad11)") (class "Default")
      (node (ref "LCD1") (pin "11") (pinfunction "DB4_11") (pintype "passive+no_connect"))
    )
    (net (code "79") (name "unconnected-(LCD1-DB5-Pad12)") (class "Default")
      (node (ref "LCD1") (pin "12") (pinfunction "DB5_12") (pintype "passive+no_connect"))
    )
    (net (code "80") (name "unconnected-(LCD1-DB6-Pad13)") (class "Default")
      (node (ref "LCD1") (pin "13") (pinfunction "DB6_13") (pintype "passive+no_connect"))
    )
    (net (code "81") (name "unconnected-(LCD1-DB7-Pad14)") (class "Default")
      (node (ref "LCD1") (pin "14") (pinfunction "DB7_14") (pintype "passive+no_connect"))
    )
    (net (code "82") (name "unconnected-(LCD1-N{slash}C-Pad16)") (class "Default")
      (node (ref "LCD1") (pin "16") (pinfunction "N/C_16") (pintype "passive+no_connect"))
    )
    (net (code "83") (name "unconnected-(LCD1-V0-Pad3)") (class "Default")
      (node (ref "LCD1") (pin "3") (pinfunction "V0_3") (pintype "passive+no_connect"))
    )
    (net (code "84") (name "unconnected-(LCD1-Vout-Pad18)") (class "Default")
      (node (ref "LCD1") (pin "18") (pinfunction "Vout_18") (pintype "passive+no_connect"))
    )
    (net (code "85") (name "unconnected-(LCD1-~{RST}-Pad17)") (class "Default")
      (node (ref "LCD1") (pin "17") (pinfunction "~{RST}_17") (pintype "passive+no_connect"))
    )
    (net (code "86") (name "unconnected-(U3-4Y-Pad12)") (class "Default")
      (node (ref "U3") (pin "12") (pinfunction "4Y_12") (pintype "output"))
    )
    (net (code "87") (name "unconnected-(U5-NC-Pad8)") (class "Default")
      (node (ref "U5") (pin "8") (pinfunction "NC_8") (pintype "passive"))
    )
    (net (code "88") (name "unconnected-(U6-NC-Pad8)") (class "Default")
      (node (ref "U6") (pin "8") (pinfunction "NC_8") (pintype "passive"))
    )
  )
)
